# Sheet1.net
KiCad netlist of a schematic drawn in Altium Designer
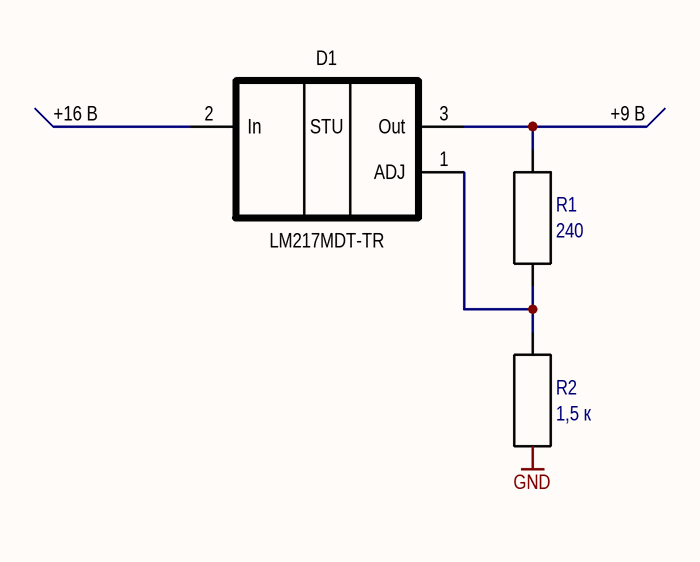
[diagram p0: Sheet1.SchDoc]

(export (version "E")
  (design (tool "Eeschema 10.0.6"))
  (components
    (comp (ref "D1") (value "LM217MDT-TR") (libsource (lib "STO") (part "LM217MDT-TR")))
    (comp (ref "R1")
      (value "240")
      (fields (field (name "Comment") "240Ом ±* *, *"))
      (libsource (lib "STO") (part "R"))
    )
    (comp (ref "R2")
      (value "1,5 к")
      (fields (field (name "Comment") "1,5 кОм ±* *, *"))
      (libsource (lib "STO") (part "R"))
    )
  )
  (nets
    (net (code "2") (name "Net-(D1-ADJ)") (class "Default")
      (node (ref "D1") (pin "1") (pinfunction "ADJ_1") (pintype "passive"))
      (node (ref "R1") (pin "2") (pinfunction "2_2") (pintype "passive"))
      (node (ref "R2") (pin "1") (pinfunction "1_1") (pintype "passive"))
    )
    (net (code "3") (name "Net-(D1-Out)") (class "Default")
      (node (ref "D1") (pin "3") (pinfunction "Out_3") (pintype "passive"))
      (node (ref "R1") (pin "1") (pinfunction "1_1") (pintype "passive"))
    )
    (net (code "4") (name "unconnected-(D1-In-Pad2)") (class "Default")
      (node (ref "D1") (pin "2") (pinfunction "In_2") (pintype "passive"))
    )
    (net (code "5") (name "unconnected-(R2-Pad2)") (class "Default")
      (node (ref "R2") (pin "2") (pinfunction "2_2") (pintype "passive"))
    )
  )
)
